# Eload_Gen_3_Power_Module_-_Input.net
KiCad netlist of a schematic drawn in Altium Designer
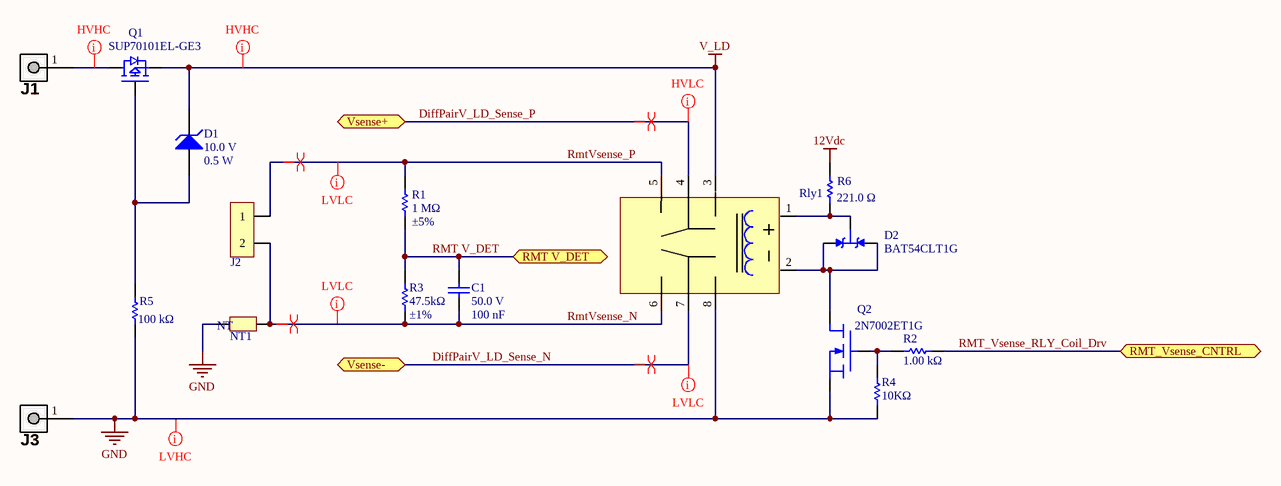
[diagram p0: Eload Gen 3 Power Module - Input.SchDoc]

(export (version "E")
  (design (tool "Eeschema 10.0.6"))
  (components
    (comp (ref "C1")
      (value "08055C104JAT2A")
      (footprint "Cap,0805")
      (description "Capacitor; Ceramic; Cap 0.1 uF; Tol 5%; Vol-Rtg 50 VDC; SMT; 0805; X7R; Tape & Reel")
      (fields (field (name "VOLTAGE RATING (DC)") "50.0 V") (field (name "CAPACITANCE") "100 nF"))
      (libsource (lib "Master JULY2019") (part "Cap,0805,100nf,50V,5%,08055C104JAT2A"))
    )
    (comp (ref "D1")
      (value "MMSZ5240BT1G")
      (footprint "SOD123")
      (description "Zener Voltage Regulator, 500 mW, 2-Pin SOD-123, Pb-Free, Tape and Reel")
      (fields (field (name "BREAKDOWN VOLTAGE") "10.0 V") (field (name "POWER RATING") "0.5 W"))
      (libsource (lib "Master JULY2019") (part "Diode, Zener,SOD-123,10V,500mW, MMSZ5240BT1G"))
    )
    (comp (ref "D2")
      (value "BAT54CLT1G")
      (footprint "SOT23-3")
      (description "BAT54CLT1G Series 30V 600 mA Dual Common Cathode Schottky Barrier Diode-SOT-23-3")
      (fields (field (name "MFG P/N") "BAT54CLT1G"))
      (libsource (lib "Master JULY2019") (part "Diode, SOT-23-3,600ma,30V,Dual Common Cathode, BAT54CLT1G"))
    )
    (comp (ref "J1")
      (value "wire teminal, lugs, screw, Keystone 8197")
      (footprint "Keystone 8197")
      (fields (field (name "MANUFACTURER PART NUMBER") "8197"))
      (libsource (lib "Master JULY2019") (part "wire teminal, lugs, screw, Keystone 8197"))
    )
    (comp (ref "J2")
      (value "TE Connectivity 282836-2")
      (footprint "TERM BLOCK 2POS SIDE ENTRY 5MM")
      (description "Wire to Board 2 Position 5 mm Pitch 30-16 AWG Euro Style Terminal Block")
      (fields (field (name "MANUFACTURER PART NUMBER") "282836-2"))
      (libsource (lib "Master JULY2019") (part "TERM BLOCK 2POS SIDE ENTRY 5MM, 282836-2"))
    )
    (comp (ref "J3")
      (value "wire teminal, lugs, screw, Keystone 8197")
      (footprint "Keystone 8197")
      (fields (field (name "MANUFACTURER PART NUMBER") "8197"))
      (libsource (lib "Master JULY2019") (part "wire teminal, lugs, screw, Keystone 8197"))
    )
    (comp (ref "NT1")
      (value "Net Tie,0.254mm")
      (footprint "0.254mm Net Tie")
      (libsource (lib "Master JULY2019") (part "Net Tie,0.254mm"))
    )
    (comp (ref "Q1")
      (value "SUP70101EL-GE3")
      (footprint "TO-220 RA")
      (description "MOSFET P-CH 100V 120A TO220AB")
      (fields (field (name "MANUFACTURER") "Vishay Siliconix"))
      (libsource (lib "Master JULY2019") (part "MOSFET,P-Chan,100V,120A,TO220, SUP70101EL-GE3"))
    )
    (comp (ref "Q2")
      (value "2N7002ET1G")
      (footprint "SOT23-3")
      (description "Small Signal MOSFET, 60 V, 310 mA, Single, N-Channel, 3-Pin SOT-23, Pb-Free, Tape and Reel")
      (fields
        (field (name "MANUFACTURER") "ON Semiconductor")
        (field (name "MANUFACTURER PART NUMBER") "2N7002ET1G")
      )
      (libsource (lib "Master JULY2019") (part "MOSFET,N-Channel,SOT23,0.25A,60V,2N7002ET1G"))
    )
    (comp (ref "R1")
      (value "CR0805-JW-105ELF")
      (footprint "res, 0805, HD")
      (description "RES SMD 1M OHM 5% 1/8W 0805")
      (fields
        (field (name "MANUFACTURER") "Bourns Inc.")
        (field (name "JLC ALT LCSC PART #") "C26108")
        (field (name "TOLERANCE") "±5%")
        (field (name "RESISTANCE") "1 MΩ")
      )
      (libsource (lib "Master JULY2019") (part "Res,0805,1MegΩ,5%,200ppm,0805W8F1005T5E"))
    )
    (comp (ref "R2")
      (value "Vishay CRCW08051K00JNEA")
      (footprint "res, 0805, HD")
      (description "Res Thick Film 0805 1K Ohm 5% 0.125W(1/8W) ±200ppm/C Molded SMD Automotive Paper T/R")
      (fields
        (field (name "MANUFACTURER PART NUMBER") "CRCW08051K00JNEA")
        (field (name "RESISTANCE") "1.00 kΩ")
      )
      (libsource (lib "Master JULY2019") (part "Res,0805,1.00 kΩ,5%,200ppm,CRCW08051K00JNEA"))
    )
    (comp (ref "R3")
      (value "RK73H2ATTD4752F")
      (footprint "res, 0805, HD")
      (fields
        (field (name "MANUFACTURER") "KOA Speer Electronics, Inc.")
        (field (name "RESISTANCE") "47.5kΩ")
        (field (name "TOLERANCE") "±1%")
      )
      (libsource (lib "Master JULY2019") (part "Res,0805,47.5KΩ,1%,100ppm,RK73H2ATTD4752F"))
    )
    (comp (ref "R4")
      (value "Vishay / Dale CRCW080510K0FKTA")
      (footprint "res, 0805, HD")
      (description "RES SMD 10K OHM 1% 1/8W 0805")
      (fields (field (name "RESISTANCE") "10KΩ"))
      (libsource (lib "Master JULY2019") (part "Res,0805,10.0kΩ,1%,100 ppm,CRCW080510K0FKTA"))
    )
    (comp (ref "R5")
      (value "CRCW0805100KFKEA")
      (footprint "res, 0805, HD")
      (description "100 kOhms ±1% 0.125W, 1/8W Chip Resistor 0805 (2012 Metric) Thick Film")
      (fields (field (name "MANUFACTURER") "Vishay") (field (name "RESISTANCE") "100 kΩ"))
      (libsource (lib "Master JULY2019") (part "Res,0805,100kΩ,1%,100ppm,CRCW0805100KFKEA"))
    )
    (comp (ref "R6")
      (value "Vishay Dale CRCW0805221RFKTA")
      (footprint "res, 0805, HD")
      (description "RES SMD 221 OHM 1% 1/8W 0805")
      (fields (field (name "RESISTANCE") "221.0 Ω"))
      (libsource (lib "Master JULY2019") (part "Res,0805,221Ω,1%,100ppm,CRCW0805221RFKTA"))
    )
    (comp (ref "Rly1")
      (value "EE2-5NU")
      (footprint "Relay,SMD,Gull Wing,DPDT (2 Form C),EE2-5NU")
      (description "RELAY GEN PURPOSE DPDT 2A 5VDC")
      (fields (field (name "MANUFACTURER") "KEMET"))
      (libsource (lib "Master JULY2019") (part "Relay,DPDT,2A,250VAC, 220VDC,5Vdc,EE2-5NU"))
    )
  )
  (nets
    (net (code "1") (name "/DiffPairV_LD_Sense_N") (class "Default")
      (node (ref "Rly1") (pin "7") (pinfunction "7_7") (pintype "passive"))
    )
    (net (code "2") (name "/DiffPairV_LD_Sense_P") (class "Default")
      (node (ref "Rly1") (pin "4") (pinfunction "4_4") (pintype "passive"))
    )
    (net (code "3") (name "/RMT V_DET") (class "Default")
      (node (ref "C1") (pin "2") (pinfunction "2_2") (pintype "passive"))
      (node (ref "R1") (pin "1") (pinfunction "1_1") (pintype "passive"))
      (node (ref "R3") (pin "2") (pinfunction "2_2") (pintype "passive"))
    )
    (net (code "4") (name "/RMT_Vsense_RLY_Coil_Drv") (class "Default")
      (node (ref "R2") (pin "2") (pinfunction "2_2") (pintype "passive"))
    )
    (net (code "5") (name "/RmtVsense_N") (class "Default")
      (node (ref "C1") (pin "1") (pinfunction "1_1") (pintype "passive"))
      (node (ref "J2") (pin "2") (pinfunction "2_2") (pintype "passive"))
      (node (ref "NT1") (pin "2") (pinfunction "2_2") (pintype "passive"))
      (node (ref "R3") (pin "1") (pinfunction "1_1") (pintype "passive"))
      (node (ref "Rly1") (pin "6") (pinfunction "6_6") (pintype "passive"))
    )
    (net (code "6") (name "/RmtVsense_P") (class "Default")
      (node (ref "J2") (pin "1") (pinfunction "1_1") (pintype "passive"))
      (node (ref "R1") (pin "2") (pinfunction "2_2") (pintype "passive"))
      (node (ref "Rly1") (pin "5") (pinfunction "5_5") (pintype "passive"))
    )
    (net (code "7") (name "12Vdc") (class "Default")
      (node (ref "R6") (pin "2") (pinfunction "2_2") (pintype "passive"))
    )
    (net (code "8") (name "GND") (class "Default")
      (node (ref "J3") (pin "1") (pinfunction "1_1") (pintype "passive"))
      (node (ref "NT1") (pin "1") (pinfunction "1_1") (pintype "passive"))
      (node (ref "Q2") (pin "2") (pinfunction "S_2") (pintype "passive"))
      (node (ref "R4") (pin "1") (pinfunction "1_1") (pintype "passive"))
      (node (ref "R5") (pin "1") (pinfunction "1_1") (pintype "passive"))
      (node (ref "Rly1") (pin "8") (pinfunction "8_8") (pintype "passive"))
    )
    (net (code "9") (name "Net-(D1-A)") (class "Default")
      (node (ref "D1") (pin "2") (pinfunction "A_2") (pintype "passive"))
      (node (ref "Q1") (pin "1") (pinfunction "Gate_1") (pintype "passive"))
      (node (ref "R5") (pin "2") (pinfunction "2_2") (pintype "passive"))
    )
    (net (code "10") (name "Net-(D2-A1)") (class "Default")
      (node (ref "D2") (pin "1") (pinfunction "A1_1") (pintype "passive"))
      (node (ref "D2") (pin "2") (pinfunction "A2_2") (pintype "passive"))
      (node (ref "Q2") (pin "3") (pinfunction "D_3") (pintype "passive"))
      (node (ref "Rly1") (pin "2") (pinfunction "C-_2") (pintype "passive"))
    )
    (net (code "11") (name "Net-(D2-C)") (class "Default")
      (node (ref "D2") (pin "3") (pinfunction "C_3") (pintype "passive"))
      (node (ref "R6") (pin "1") (pinfunction "1_1") (pintype "passive"))
      (node (ref "Rly1") (pin "1") (pinfunction "C+_1") (pintype "passive"))
    )
    (net (code "12") (name "Net-(Q1-Drain)") (class "Default")
      (node (ref "J1") (pin "1") (pinfunction "1_1") (pintype "passive"))
      (node (ref "Q1") (pin "2") (pinfunction "Drain_2") (pintype "passive"))
    )
    (net (code "13") (name "Net-(Q2-G)") (class "Default")
      (node (ref "Q2") (pin "1") (pinfunction "G_1") (pintype "passive"))
      (node (ref "R2") (pin "1") (pinfunction "1_1") (pintype "passive"))
      (node (ref "R4") (pin "2") (pinfunction "2_2") (pintype "passive"))
    )
    (net (code "14") (name "V_LD") (class "Default")
      (node (ref "D1") (pin "1") (pinfunction "K_1") (pintype "passive"))
      (node (ref "Q1") (pin "3") (pinfunction "Source_3") (pintype "passive"))
      (node (ref "Rly1") (pin "3") (pinfunction "3_3") (pintype "passive"))
    )
  )
)
